# ESP-WROOM-02-ASIF-12.net
KiCad netlist of a schematic drawn in EAGLE
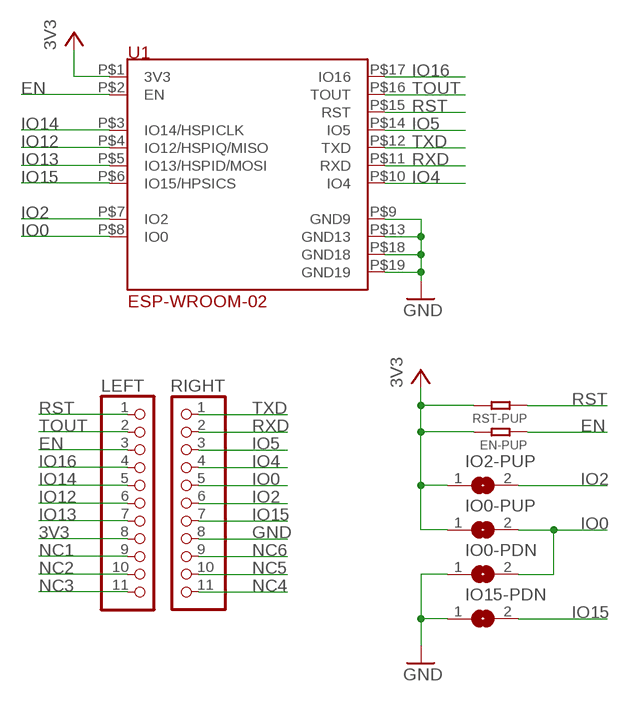
[diagram p0: schematic, sheet 1]

(export (version "E")
  (design (tool "Eeschema 10.0.6"))
  (components
    (comp (ref "EN-PUP")
      (value "10K")
      (footprint "eagle-import:R0805")
      (fields (field (name "MPN") "RC0805FR-0710KL"))
      (libsource (lib "eagle-import") (part "SMD-RES-10K-1%-1/8W(0805)"))
    )
    (comp (ref "IO0-PDN")
      (value "SJ")
      (footprint "eagle-import:SJ")
      (libsource (lib "eagle-import") (part "SJ"))
    )
    (comp (ref "IO0-PUP")
      (value "SJ")
      (footprint "eagle-import:SJ")
      (libsource (lib "eagle-import") (part "SJ"))
    )
    (comp (ref "IO2-PUP")
      (value "SJ")
      (footprint "eagle-import:SJ")
      (libsource (lib "eagle-import") (part "SJ"))
    )
    (comp (ref "IO15-PDN")
      (value "SJ")
      (footprint "eagle-import:SJ")
      (libsource (lib "eagle-import") (part "SJ"))
    )
    (comp (ref "LEFT")
      (value "PINHD-1X11OCT")
      (footprint "eagle-import:1X11OCT")
      (libsource (lib "eagle-import") (part "PINHD-1X11OCT"))
    )
    (comp (ref "RIGHT")
      (value "PINHD-1X11OCT")
      (footprint "eagle-import:1X11OCT")
      (libsource (lib "eagle-import") (part "PINHD-1X11OCT"))
    )
    (comp (ref "RST-PUP")
      (value "10K")
      (footprint "eagle-import:R0805")
      (fields (field (name "MPN") "RC0805FR-0710KL"))
      (libsource (lib "eagle-import") (part "SMD-RES-10K-1%-1/8W(0805)"))
    )
    (comp (ref "U1")
      (value "ESP-WROOM-02")
      (footprint "eagle-import:ESP-WROOM-02")
      (libsource (lib "eagle-import") (part "ESP-WROOM-02"))
    )
  )
  (nets
    (net (code "1") (name "/EN") (class "Default")
      (node (ref "EN-PUP") (pin "1") (pinfunction "1_1") (pintype "passive"))
      (node (ref "LEFT") (pin "3") (pinfunction "3_3") (pintype "passive"))
      (node (ref "U1") (pin "P$2") (pinfunction "EN_P$2") (pintype "bidirectional"))
    )
    (net (code "2") (name "/IO0") (class "Default")
      (node (ref "IO0-PDN") (pin "2") (pinfunction "2_2") (pintype "passive"))
      (node (ref "IO0-PUP") (pin "2") (pinfunction "2_2") (pintype "passive"))
      (node (ref "RIGHT") (pin "5") (pinfunction "5_5") (pintype "passive"))
      (node (ref "U1") (pin "P$8") (pinfunction "IO0_P$8") (pintype "bidirectional"))
    )
    (net (code "3") (name "/IO2") (class "Default")
      (node (ref "IO2-PUP") (pin "2") (pinfunction "2_2") (pintype "passive"))
      (node (ref "RIGHT") (pin "6") (pinfunction "6_6") (pintype "passive"))
      (node (ref "U1") (pin "P$7") (pinfunction "IO2_P$7") (pintype "bidirectional"))
    )
    (net (code "4") (name "/IO4") (class "Default")
      (node (ref "RIGHT") (pin "4") (pinfunction "4_4") (pintype "passive"))
      (node (ref "U1") (pin "P$10") (pinfunction "IO4_P$10") (pintype "bidirectional"))
    )
    (net (code "5") (name "/IO5") (class "Default")
      (node (ref "RIGHT") (pin "3") (pinfunction "3_3") (pintype "passive"))
      (node (ref "U1") (pin "P$14") (pinfunction "IO5_P$14") (pintype "bidirectional"))
    )
    (net (code "6") (name "/IO12") (class "Default")
      (node (ref "LEFT") (pin "6") (pinfunction "6_6") (pintype "passive"))
      (node (ref "U1") (pin "P$4") (pinfunction "IO12/HSPIQ/MISO_P$4") (pintype "bidirectional"))
    )
    (net (code "7") (name "/IO13") (class "Default")
      (node (ref "LEFT") (pin "7") (pinfunction "7_7") (pintype "passive"))
      (node (ref "U1") (pin "P$5") (pinfunction "IO13/HSPID/MOSI_P$5") (pintype "bidirectional"))
    )
    (net (code "8") (name "/IO14") (class "Default")
      (node (ref "LEFT") (pin "5") (pinfunction "5_5") (pintype "passive"))
      (node (ref "U1") (pin "P$3") (pinfunction "IO14/HSPICLK_P$3") (pintype "bidirectional"))
    )
    (net (code "9") (name "/IO15") (class "Default")
      (node (ref "IO15-PDN") (pin "2") (pinfunction "2_2") (pintype "passive"))
      (node (ref "RIGHT") (pin "7") (pinfunction "7_7") (pintype "passive"))
      (node (ref "U1") (pin "P$6") (pinfunction "IO15/HPSICS_P$6") (pintype "bidirectional"))
    )
    (net (code "10") (name "/IO16") (class "Default")
      (node (ref "LEFT") (pin "4") (pinfunction "4_4") (pintype "passive"))
      (node (ref "U1") (pin "P$17") (pinfunction "IO16_P$17") (pintype "bidirectional"))
    )
    (net (code "11") (name "/NC1") (class "Default")
      (node (ref "LEFT") (pin "9") (pinfunction "9_9") (pintype "passive"))
    )
    (net (code "12") (name "/NC2") (class "Default")
      (node (ref "LEFT") (pin "10") (pinfunction "10_10") (pintype "passive"))
    )
    (net (code "13") (name "/NC3") (class "Default")
      (node (ref "LEFT") (pin "11") (pinfunction "11_11") (pintype "passive"))
    )
    (net (code "14") (name "/NC4") (class "Default")
      (node (ref "RIGHT") (pin "11") (pinfunction "11_11") (pintype "passive"))
    )
    (net (code "15") (name "/NC5") (class "Default")
      (node (ref "RIGHT") (pin "10") (pinfunction "10_10") (pintype "passive"))
    )
    (net (code "16") (name "/NC6") (class "Default")
      (node (ref "RIGHT") (pin "9") (pinfunction "9_9") (pintype "passive"))
    )
    (net (code "17") (name "/RST") (class "Default")
      (node (ref "LEFT") (pin "1") (pinfunction "1_1") (pintype "passive"))
      (node (ref "RST-PUP") (pin "1") (pinfunction "1_1") (pintype "passive"))
      (node (ref "U1") (pin "P$15") (pinfunction "RST_P$15") (pintype "bidirectional"))
    )
    (net (code "18") (name "/RXD") (class "Default")
      (node (ref "RIGHT") (pin "2") (pinfunction "2_2") (pintype "passive"))
      (node (ref "U1") (pin "P$11") (pinfunction "RXD_P$11") (pintype "bidirectional"))
    )
    (net (code "19") (name "/TOUT") (class "Default")
      (node (ref "LEFT") (pin "2") (pinfunction "2_2") (pintype "passive"))
      (node (ref "U1") (pin "P$16") (pinfunction "TOUT_P$16") (pintype "bidirectional"))
    )
    (net (code "20") (name "/TXD") (class "Default")
      (node (ref "RIGHT") (pin "1") (pinfunction "1_1") (pintype "passive"))
      (node (ref "U1") (pin "P$12") (pinfunction "TXD_P$12") (pintype "bidirectional"))
    )
    (net (code "21") (name "3V3") (class "Default")
      (node (ref "EN-PUP") (pin "2") (pinfunction "2_2") (pintype "passive"))
      (node (ref "IO0-PUP") (pin "1") (pinfunction "1_1") (pintype "passive"))
      (node (ref "IO2-PUP") (pin "1") (pinfunction "1_1") (pintype "passive"))
      (node (ref "LEFT") (pin "8") (pinfunction "8_8") (pintype "passive"))
      (node (ref "RST-PUP") (pin "2") (pinfunction "2_2") (pintype "passive"))
      (node (ref "U1") (pin "P$1") (pinfunction "3V3_P$1") (pintype "bidirectional"))
    )
    (net (code "22") (name "GND") (class "Default")
      (node (ref "IO0-PDN") (pin "1") (pinfunction "1_1") (pintype "passive"))
      (node (ref "IO15-PDN") (pin "1") (pinfunction "1_1") (pintype "passive"))
      (node (ref "RIGHT") (pin "8") (pinfunction "8_8") (pintype "passive"))
      (node (ref "U1") (pin "P$13") (pinfunction "GND13_P$13") (pintype "bidirectional"))
      (node (ref "U1") (pin "P$18") (pinfunction "GND18_P$18") (pintype "bidirectional"))
      (node (ref "U1") (pin "P$19") (pinfunction "GND19_P$19") (pintype "bidirectional"))
      (node (ref "U1") (pin "P$9") (pinfunction "GND9_P$9") (pintype "bidirectional"))
    )
  )
)
